# 8085_IO_LCD.net
KiCad netlist of a schematic drawn in EAGLE
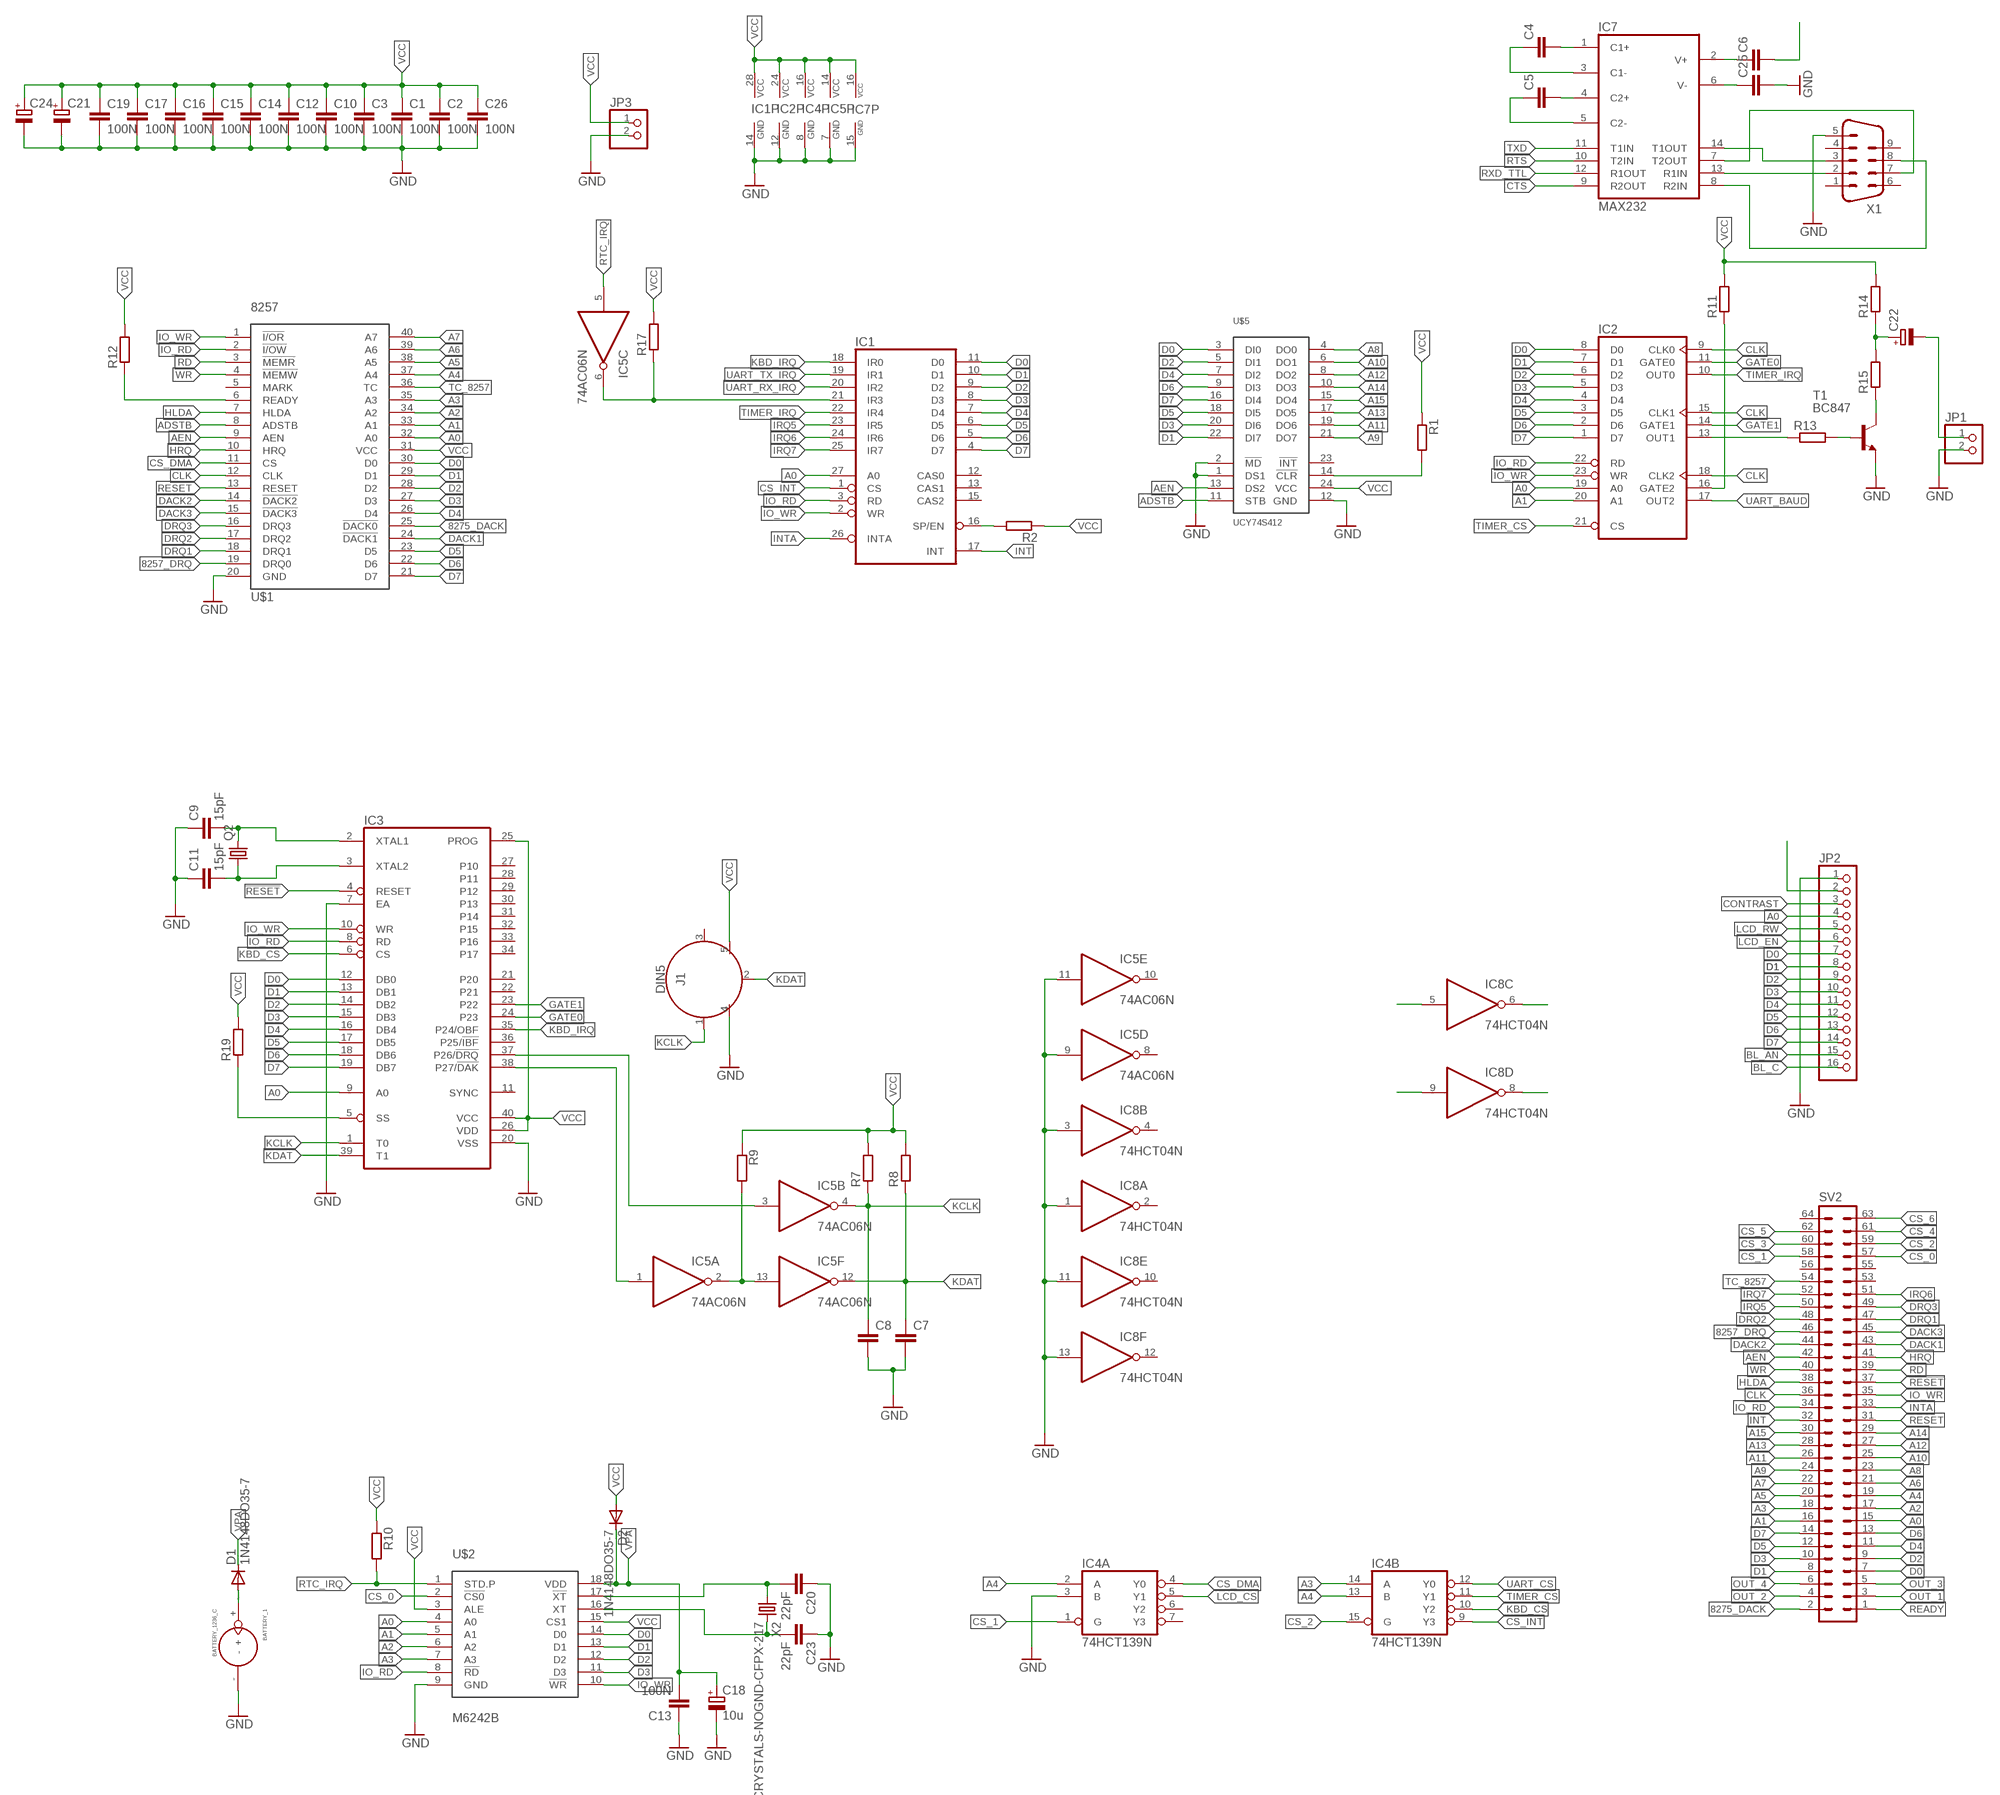
[diagram p0: schematic, sheet 1, part 1 of 2]
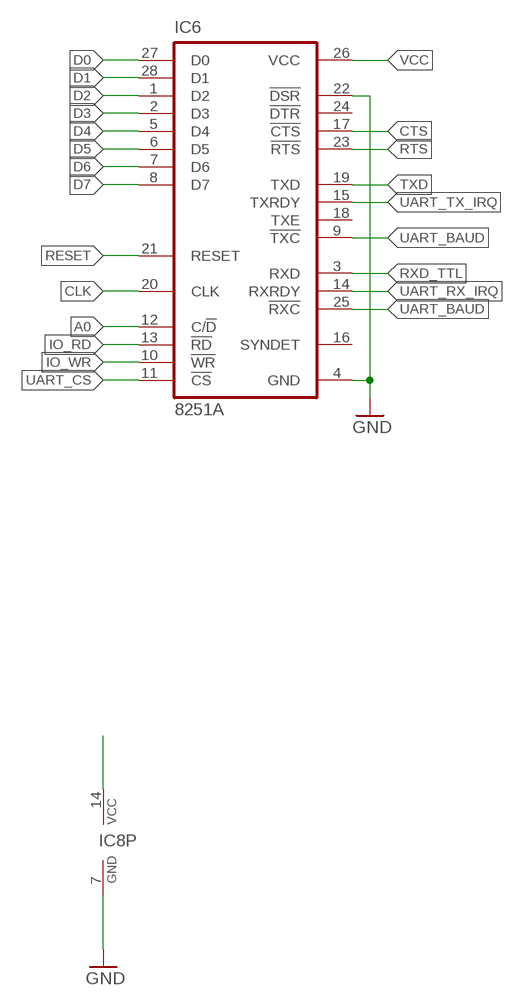
[diagram p1: schematic, sheet 1, part 2 of 2]

(export (version "E")
  (design (tool "Eeschema 10.0.6"))
  (components
    (comp (ref "BATTERY_1")
      (value "BATTERY_1236_C")
      (footprint "eagle-import:BATTERY_1236_C")
      (libsource (lib "eagle-import") (part "BATTERY_1236_C"))
    )
    (comp (ref "C1")
      (value "100N")
      (footprint "eagle-import:C0603")
      (libsource (lib "eagle-import") (part "C-EUC0603"))
    )
    (comp (ref "C2")
      (value "100N")
      (footprint "eagle-import:C1206")
      (libsource (lib "eagle-import") (part "C-EUC1206"))
    )
    (comp (ref "C3")
      (value "100N")
      (footprint "eagle-import:C0603")
      (libsource (lib "eagle-import") (part "C-EUC0603"))
    )
    (comp (ref "C4")
      (value "C-EUC0603")
      (footprint "eagle-import:C0603")
      (libsource (lib "eagle-import") (part "C-EUC0603"))
    )
    (comp (ref "C5")
      (value "C-EUC0603")
      (footprint "eagle-import:C0603")
      (libsource (lib "eagle-import") (part "C-EUC0603"))
    )
    (comp (ref "C6")
      (value "C-EUC0603")
      (footprint "eagle-import:C0603")
      (libsource (lib "eagle-import") (part "C-EUC0603"))
    )
    (comp (ref "C7")
      (value "C-EUC0603")
      (footprint "eagle-import:C0603")
      (libsource (lib "eagle-import") (part "C-EUC0603"))
    )
    (comp (ref "C8")
      (value "C-EUC0603")
      (footprint "eagle-import:C0603")
      (libsource (lib "eagle-import") (part "C-EUC0603"))
    )
    (comp (ref "C9")
      (value "15pF")
      (footprint "eagle-import:C0603")
      (libsource (lib "eagle-import") (part "C-EUC0603"))
    )
    (comp (ref "C10")
      (value "100N")
      (footprint "eagle-import:C0603")
      (libsource (lib "eagle-import") (part "C-EUC0603"))
    )
    (comp (ref "C11")
      (value "15pF")
      (footprint "eagle-import:C0603")
      (libsource (lib "eagle-import") (part "C-EUC0603"))
    )
    (comp (ref "C12")
      (value "100N")
      (footprint "eagle-import:C0603")
      (libsource (lib "eagle-import") (part "C-EUC0603"))
    )
    (comp (ref "C13")
      (value "100N")
      (footprint "eagle-import:C0603")
      (libsource (lib "eagle-import") (part "C-EUC0603"))
    )
    (comp (ref "C14")
      (value "100N")
      (footprint "eagle-import:C0603")
      (libsource (lib "eagle-import") (part "C-EUC0603"))
    )
    (comp (ref "C15")
      (value "100N")
      (footprint "eagle-import:C0603")
      (libsource (lib "eagle-import") (part "C-EUC0603"))
    )
    (comp (ref "C16")
      (value "100N")
      (footprint "eagle-import:C0603")
      (libsource (lib "eagle-import") (part "C-EUC0603"))
    )
    (comp (ref "C17")
      (value "100N")
      (footprint "eagle-import:C0603")
      (libsource (lib "eagle-import") (part "C-EUC0603"))
    )
    (comp (ref "C18")
      (value "10u")
      (footprint "eagle-import:SMC_B")
      (libsource (lib "eagle-import") (part "CPOL-EUSMCB"))
    )
    (comp (ref "C19")
      (value "100N")
      (footprint "eagle-import:C0603")
      (libsource (lib "eagle-import") (part "C-EUC0603"))
    )
    (comp (ref "C20")
      (value "22pF")
      (footprint "eagle-import:C0603")
      (libsource (lib "eagle-import") (part "C-EUC0603"))
    )
    (comp (ref "C21")
      (value "CPOL-EUE3.5-8")
      (footprint "eagle-import:E3,5-8")
      (libsource (lib "eagle-import") (part "CPOL-EUE3.5-8"))
    )
    (comp (ref "C22")
      (value "CPOL-EUE2-4")
      (footprint "eagle-import:E2-4")
      (libsource (lib "eagle-import") (part "CPOL-EUE2-4"))
    )
    (comp (ref "C23")
      (value "22pF")
      (footprint "eagle-import:C0603")
      (libsource (lib "eagle-import") (part "C-EUC0603"))
    )
    (comp (ref "C24")
      (value "CPOL-EUSMCB")
      (footprint "eagle-import:SMC_B")
      (libsource (lib "eagle-import") (part "CPOL-EUSMCB"))
    )
    (comp (ref "C25")
      (value "C-EUC0603")
      (footprint "eagle-import:C0603")
      (libsource (lib "eagle-import") (part "C-EUC0603"))
    )
    (comp (ref "C26")
      (value "100N")
      (footprint "eagle-import:C0805")
      (libsource (lib "eagle-import") (part "C-EUC0805"))
    )
    (comp (ref "D1")
      (value "1N4148DO35-7")
      (footprint "eagle-import:DO35-7")
      (libsource (lib "eagle-import") (part "1N4148DO35-7"))
    )
    (comp (ref "D2")
      (value "1N4148DO35-7")
      (footprint "eagle-import:DO35-7")
      (libsource (lib "eagle-import") (part "1N4148DO35-7"))
    )
    (comp (ref "IC1")
      (value "8259A")
      (footprint "eagle-import:DIL28-6")
      (libsource (lib "eagle-import") (part "8259A"))
    )
    (comp (ref "IC2")
      (value "8253")
      (footprint "eagle-import:DIL24-6")
      (libsource (lib "eagle-import") (part "8253"))
    )
    (comp (ref "IC3")
      (value "UPI-8042AH")
      (footprint "eagle-import:DIL40")
      (libsource (lib "eagle-import") (part "UPI-8042AH"))
    )
    (comp (ref "IC4")
      (value "74HCT139N")
      (footprint "eagle-import:DIL16")
      (libsource (lib "eagle-import") (part "74139NHCT"))
    )
    (comp (ref "IC5")
      (value "74AC06N")
      (footprint "eagle-import:DIL14")
      (libsource (lib "eagle-import") (part "7406NAC"))
    )
    (comp (ref "IC6")
      (value "8251A")
      (footprint "eagle-import:DIL28-6")
      (libsource (lib "eagle-import") (part "8251A"))
    )
    (comp (ref "IC7")
      (value "MAX232")
      (footprint "eagle-import:DIL16")
      (fields (field (name "MF") "MAXIM") (field (name "MPN") "MAX232ACPE+"))
      (libsource (lib "eagle-import") (part "MAX232"))
    )
    (comp (ref "IC8")
      (value "74HCT04N")
      (footprint "eagle-import:DIL14")
      (libsource (lib "eagle-import") (part "7404NHCT"))
    )
    (comp (ref "J1")
      (value "DIN5")
      (footprint "eagle-import:DIN5-RA-PTH")
      (libsource (lib "eagle-import") (part "DIN5"))
    )
    (comp (ref "JP1")
      (value "PINHD-1X2")
      (footprint "eagle-import:1X02")
      (libsource (lib "eagle-import") (part "PINHD-1X2"))
    )
    (comp (ref "JP2")
      (value "PINHD-1X16")
      (footprint "eagle-import:1X16")
      (libsource (lib "eagle-import") (part "PINHD-1X16"))
    )
    (comp (ref "JP3")
      (value "PINHD-1X2/90")
      (footprint "eagle-import:1X02_90")
      (libsource (lib "eagle-import") (part "PINHD-1X2/90"))
    )
    (comp (ref "Q2")
      (value "CRYSTALHC49S")
      (footprint "eagle-import:HC49_S")
      (libsource (lib "eagle-import") (part "CRYSTALHC49S"))
    )
    (comp (ref "R1")
      (value "R-EU_R0603")
      (footprint "eagle-import:R0603")
      (libsource (lib "eagle-import") (part "R-EU_R0603"))
    )
    (comp (ref "R2")
      (value "R-EU_R0603")
      (footprint "eagle-import:R0603")
      (libsource (lib "eagle-import") (part "R-EU_R0603"))
    )
    (comp (ref "R7")
      (value "R-EU_0204/5")
      (footprint "eagle-import:0204_5")
      (libsource (lib "eagle-import") (part "R-EU_0204/5"))
    )
    (comp (ref "R8")
      (value "R-EU_M0805")
      (footprint "eagle-import:M0805")
      (libsource (lib "eagle-import") (part "R-EU_M0805"))
    )
    (comp (ref "R9")
      (value "R-EU_R0603")
      (footprint "eagle-import:R0603")
      (libsource (lib "eagle-import") (part "R-EU_R0603"))
    )
    (comp (ref "R10")
      (value "R-EU_R0603")
      (footprint "eagle-import:R0603")
      (libsource (lib "eagle-import") (part "R-EU_R0603"))
    )
    (comp (ref "R11")
      (value "R-EU_R0603")
      (footprint "eagle-import:R0603")
      (libsource (lib "eagle-import") (part "R-EU_R0603"))
    )
    (comp (ref "R12")
      (value "R-EU_R0603")
      (footprint "eagle-import:R0603")
      (libsource (lib "eagle-import") (part "R-EU_R0603"))
    )
    (comp (ref "R13")
      (value "R-EU_R0603")
      (footprint "eagle-import:R0603")
      (libsource (lib "eagle-import") (part "R-EU_R0603"))
    )
    (comp (ref "R14")
      (value "R-EU_0204/5")
      (footprint "eagle-import:0204_5")
      (libsource (lib "eagle-import") (part "R-EU_0204/5"))
    )
    (comp (ref "R15")
      (value "R-EU_R0603")
      (footprint "eagle-import:R0603")
      (libsource (lib "eagle-import") (part "R-EU_R0603"))
    )
    (comp (ref "R17")
      (value "R-EU_0204/7")
      (footprint "eagle-import:0204_7")
      (libsource (lib "eagle-import") (part "R-EU_0204/7"))
    )
    (comp (ref "R19")
      (value "R-EU_0204/5")
      (footprint "eagle-import:0204_5")
      (libsource (lib "eagle-import") (part "R-EU_0204/5"))
    )
    (comp (ref "SV2")
      (value "ML64L")
      (footprint "eagle-import:ML64L")
      (libsource (lib "eagle-import") (part "ML64L"))
    )
    (comp (ref "T1")
      (value "BC847")
      (footprint "eagle-import:SOT23")
      (libsource (lib "eagle-import") (part "BC847"))
    )
    (comp (ref "U$1")
      (value "8257")
      (footprint "eagle-import:DIL40")
      (libsource (lib "eagle-import") (part "8257"))
    )
    (comp (ref "U$2")
      (value "M6242B")
      (footprint "eagle-import:DIL18")
      (libsource (lib "eagle-import") (part "M6242B"))
    )
    (comp (ref "U$5")
      (value "UCY74S412")
      (footprint "eagle-import:DIL24-6")
      (libsource (lib "eagle-import") (part "UCY74S412"))
    )
    (comp (ref "X1")
      (value "M09HP")
      (footprint "eagle-import:M09HP")
      (libsource (lib "eagle-import") (part "M09HP"))
    )
    (comp (ref "X2")
      (value "CRYSTALS-NOGND-CFPX-217")
      (footprint "eagle-import:3.2X1.5-2-PAD")
      (libsource (lib "eagle-import") (part "CRYSTALS-NOGND-CFPX-217"))
    )
  )
  (nets
    (net (code "1") (name "/~{RESET}") (class "Default")
      (node (ref "IC3") (pin "4") (pinfunction "RESET_4") (pintype "input"))
      (node (ref "SV2") (pin "37") (pinfunction "37_37") (pintype "passive"))
    )
    (net (code "2") (name "8257_DRQ") (class "Default")
      (node (ref "SV2") (pin "46") (pinfunction "46_46") (pintype "passive"))
      (node (ref "U$1") (pin "19") (pinfunction "DRQ0_19") (pintype "bidirectional"))
    )
    (net (code "3") (name "8275_DACK") (class "Default")
      (node (ref "SV2") (pin "2") (pinfunction "2_2") (pintype "passive"))
      (node (ref "U$1") (pin "25") (pinfunction "~{DACK0}_25") (pintype "bidirectional"))
    )
    (net (code "4") (name "A0") (class "Default")
      (node (ref "IC1") (pin "27") (pinfunction "A0_27") (pintype "input"))
      (node (ref "IC2") (pin "19") (pinfunction "A0_19") (pintype "input"))
      (node (ref "IC3") (pin "9") (pinfunction "A0_9") (pintype "input"))
      (node (ref "IC6") (pin "12") (pinfunction "C/~{D}_12") (pintype "input"))
      (node (ref "JP2") (pin "4") (pinfunction "4_4") (pintype "passive"))
      (node (ref "SV2") (pin "15") (pinfunction "15_15") (pintype "passive"))
      (node (ref "U$1") (pin "32") (pinfunction "A0_32") (pintype "bidirectional"))
      (node (ref "U$2") (pin "4") (pinfunction "A0_4") (pintype "bidirectional"))
    )
    (net (code "5") (name "A1") (class "Default")
      (node (ref "IC2") (pin "20") (pinfunction "A1_20") (pintype "input"))
      (node (ref "SV2") (pin "16") (pinfunction "16_16") (pintype "passive"))
      (node (ref "U$1") (pin "33") (pinfunction "A1_33") (pintype "bidirectional"))
      (node (ref "U$2") (pin "5") (pinfunction "A1_5") (pintype "bidirectional"))
    )
    (net (code "6") (name "A2") (class "Default")
      (node (ref "SV2") (pin "17") (pinfunction "17_17") (pintype "passive"))
      (node (ref "U$1") (pin "34") (pinfunction "A2_34") (pintype "bidirectional"))
      (node (ref "U$2") (pin "6") (pinfunction "A2_6") (pintype "bidirectional"))
    )
    (net (code "7") (name "A3") (class "Default")
      (node (ref "IC4") (pin "14") (pinfunction "A_14") (pintype "input"))
      (node (ref "SV2") (pin "18") (pinfunction "18_18") (pintype "passive"))
      (node (ref "U$1") (pin "35") (pinfunction "A3_35") (pintype "bidirectional"))
      (node (ref "U$2") (pin "7") (pinfunction "A3_7") (pintype "bidirectional"))
    )
    (net (code "8") (name "A4") (class "Default")
      (node (ref "IC4") (pin "13") (pinfunction "B_13") (pintype "input"))
      (node (ref "IC4") (pin "2") (pinfunction "A_2") (pintype "input"))
      (node (ref "SV2") (pin "19") (pinfunction "19_19") (pintype "passive"))
      (node (ref "U$1") (pin "37") (pinfunction "A4_37") (pintype "bidirectional"))
    )
    (net (code "9") (name "A5") (class "Default")
      (node (ref "SV2") (pin "20") (pinfunction "20_20") (pintype "passive"))
      (node (ref "U$1") (pin "38") (pinfunction "A5_38") (pintype "bidirectional"))
    )
    (net (code "10") (name "A6") (class "Default")
      (node (ref "SV2") (pin "21") (pinfunction "21_21") (pintype "passive"))
      (node (ref "U$1") (pin "39") (pinfunction "A6_39") (pintype "bidirectional"))
    )
    (net (code "11") (name "A7") (class "Default")
      (node (ref "SV2") (pin "22") (pinfunction "22_22") (pintype "passive"))
      (node (ref "U$1") (pin "40") (pinfunction "A7_40") (pintype "bidirectional"))
    )
    (net (code "12") (name "A8") (class "Default")
      (node (ref "SV2") (pin "23") (pinfunction "23_23") (pintype "passive"))
      (node (ref "U$5") (pin "4") (pinfunction "DO0_4") (pintype "bidirectional"))
    )
    (net (code "13") (name "A9") (class "Default")
      (node (ref "SV2") (pin "24") (pinfunction "24_24") (pintype "passive"))
      (node (ref "U$5") (pin "21") (pinfunction "DO7_21") (pintype "bidirectional"))
    )
    (net (code "14") (name "A10") (class "Default")
      (node (ref "SV2") (pin "25") (pinfunction "25_25") (pintype "passive"))
      (node (ref "U$5") (pin "6") (pinfunction "DO1_6") (pintype "bidirectional"))
    )
    (net (code "15") (name "A11") (class "Default")
      (node (ref "SV2") (pin "26") (pinfunction "26_26") (pintype "passive"))
      (node (ref "U$5") (pin "19") (pinfunction "DO6_19") (pintype "bidirectional"))
    )
    (net (code "16") (name "A12") (class "Default")
      (node (ref "SV2") (pin "27") (pinfunction "27_27") (pintype "passive"))
      (node (ref "U$5") (pin "8") (pinfunction "DO2_8") (pintype "bidirectional"))
    )
    (net (code "17") (name "A13") (class "Default")
      (node (ref "SV2") (pin "28") (pinfunction "28_28") (pintype "passive"))
      (node (ref "U$5") (pin "17") (pinfunction "DO5_17") (pintype "bidirectional"))
    )
    (net (code "18") (name "A14") (class "Default")
      (node (ref "SV2") (pin "29") (pinfunction "29_29") (pintype "passive"))
      (node (ref "U$5") (pin "10") (pinfunction "DO3_10") (pintype "bidirectional"))
    )
    (net (code "19") (name "A15") (class "Default")
      (node (ref "SV2") (pin "30") (pinfunction "30_30") (pintype "passive"))
      (node (ref "U$5") (pin "15") (pinfunction "DO4_15") (pintype "bidirectional"))
    )
    (net (code "20") (name "ADSTB") (class "Default")
      (node (ref "U$1") (pin "8") (pinfunction "ADSTB_8") (pintype "bidirectional"))
      (node (ref "U$5") (pin "11") (pinfunction "STB_11") (pintype "bidirectional"))
    )
    (net (code "21") (name "AEN") (class "Default")
      (node (ref "SV2") (pin "42") (pinfunction "42_42") (pintype "passive"))
      (node (ref "U$1") (pin "9") (pinfunction "AEN_9") (pintype "bidirectional"))
      (node (ref "U$5") (pin "13") (pinfunction "DS2_13") (pintype "bidirectional"))
    )
    (net (code "22") (name "BL_AN") (class "Default")
      (node (ref "JP2") (pin "15") (pinfunction "15_15") (pintype "passive"))
    )
    (net (code "23") (name "BL_C") (class "Default")
      (node (ref "JP2") (pin "16") (pinfunction "16_16") (pintype "passive"))
    )
    (net (code "24") (name "CLK") (class "Default")
      (node (ref "IC2") (pin "15") (pinfunction "CLK1_15") (pintype "input"))
      (node (ref "IC2") (pin "18") (pinfunction "CLK2_18") (pintype "input"))
      (node (ref "IC2") (pin "9") (pinfunction "CLK0_9") (pintype "input"))
      (node (ref "IC6") (pin "20") (pinfunction "CLK_20") (pintype "input"))
      (node (ref "SV2") (pin "36") (pinfunction "36_36") (pintype "passive"))
      (node (ref "U$1") (pin "12") (pinfunction "CLK_12") (pintype "bidirectional"))
    )
    (net (code "25") (name "CONTRAST") (class "Default")
      (node (ref "JP2") (pin "3") (pinfunction "3_3") (pintype "passive"))
    )
    (net (code "26") (name "CS_0") (class "Default")
      (node (ref "SV2") (pin "57") (pinfunction "57_57") (pintype "passive"))
      (node (ref "U$2") (pin "2") (pinfunction "~{CS0}_2") (pintype "bidirectional"))
    )
    (net (code "27") (name "CS_1") (class "Default")
      (node (ref "IC4") (pin "1") (pinfunction "G_1") (pintype "input"))
      (node (ref "SV2") (pin "58") (pinfunction "58_58") (pintype "passive"))
    )
    (net (code "28") (name "CS_2") (class "Default")
      (node (ref "IC4") (pin "15") (pinfunction "G_15") (pintype "input"))
      (node (ref "SV2") (pin "59") (pinfunction "59_59") (pintype "passive"))
    )
    (net (code "29") (name "CS_3") (class "Default")
      (node (ref "SV2") (pin "60") (pinfunction "60_60") (pintype "passive"))
    )
    (net (code "30") (name "CS_4") (class "Default")
      (node (ref "SV2") (pin "61") (pinfunction "61_61") (pintype "passive"))
    )
    (net (code "31") (name "CS_5") (class "Default")
      (node (ref "SV2") (pin "62") (pinfunction "62_62") (pintype "passive"))
    )
    (net (code "32") (name "CS_6") (class "Default")
      (node (ref "SV2") (pin "63") (pinfunction "63_63") (pintype "passive"))
    )
    (net (code "33") (name "CS_DMA") (class "Default")
      (node (ref "IC4") (pin "4") (pinfunction "Y0_4") (pintype "output"))
      (node (ref "U$1") (pin "11") (pinfunction "CS_11") (pintype "bidirectional"))
    )
    (net (code "34") (name "CS_INT") (class "Default")
      (node (ref "IC1") (pin "1") (pinfunction "CS_1") (pintype "input"))
      (node (ref "IC4") (pin "9") (pinfunction "Y3_9") (pintype "output"))
    )
    (net (code "35") (name "CTS") (class "Default")
      (node (ref "IC6") (pin "17") (pinfunction "~{CTS}_17") (pintype "input"))
      (node (ref "IC7") (pin "9") (pinfunction "R2OUT_9") (pintype "output"))
    )
    (net (code "36") (name "D0") (class "Default")
      (node (ref "IC1") (pin "11") (pinfunction "D0_11") (pintype "bidirectional"))
      (node (ref "IC2") (pin "8") (pinfunction "D0_8") (pintype "bidirectional"))
      (node (ref "IC3") (pin "12") (pinfunction "DB0_12") (pintype "bidirectional"))
      (node (ref "IC6") (pin "27") (pinfunction "D0_27") (pintype "tri_state"))
      (node (ref "JP2") (pin "7") (pinfunction "7_7") (pintype "passive"))
      (node (ref "SV2") (pin "7") (pinfunction "7_7") (pintype "passive"))
      (node (ref "U$1") (pin "30") (pinfunction "D0_30") (pintype "bidirectional"))
      (node (ref "U$2") (pin "14") (pinfunction "D0_14") (pintype "bidirectional"))
      (node (ref "U$5") (pin "3") (pinfunction "DI0_3") (pintype "bidirectional"))
    )
    (net (code "37") (name "D1") (class "Default")
      (node (ref "IC1") (pin "10") (pinfunction "D1_10") (pintype "bidirectional"))
      (node (ref "IC2") (pin "7") (pinfunction "D1_7") (pintype "bidirectional"))
      (node (ref "IC3") (pin "13") (pinfunction "DB1_13") (pintype "bidirectional"))
      (node (ref "IC6") (pin "28") (pinfunction "D1_28") (pintype "tri_state"))
      (node (ref "JP2") (pin "8") (pinfunction "8_8") (pintype "passive"))
      (node (ref "SV2") (pin "8") (pinfunction "8_8") (pintype "passive"))
      (node (ref "U$1") (pin "29") (pinfunction "D1_29") (pintype "bidirectional"))
      (node (ref "U$2") (pin "13") (pinfunction "D1_13") (pintype "bidirectional"))
      (node (ref "U$5") (pin "22") (pinfunction "DI7_22") (pintype "bidirectional"))
    )
    (net (code "38") (name "D2") (class "Default")
      (node (ref "IC1") (pin "9") (pinfunction "D2_9") (pintype "bidirectional"))
      (node (ref "IC2") (pin "6") (pinfunction "D2_6") (pintype "bidirectional"))
      (node (ref "IC3") (pin "14") (pinfunction "DB2_14") (pintype "bidirectional"))
      (node (ref "IC6") (pin "1") (pinfunction "D2_1") (pintype "tri_state"))
      (node (ref "JP2") (pin "9") (pinfunction "9_9") (pintype "passive"))
      (node (ref "SV2") (pin "9") (pinfunction "9_9") (pintype "passive"))
      (node (ref "U$1") (pin "28") (pinfunction "D2_28") (pintype "bidirectional"))
      (node (ref "U$2") (pin "12") (pinfunction "D2_12") (pintype "bidirectional"))
      (node (ref "U$5") (pin "5") (pinfunction "DI1_5") (pintype "bidirectional"))
    )
    (net (code "39") (name "D3") (class "Default")
      (node (ref "IC1") (pin "8") (pinfunction "D3_8") (pintype "bidirectional"))
      (node (ref "IC2") (pin "5") (pinfunction "D3_5") (pintype "bidirectional"))
      (node (ref "IC3") (pin "15") (pinfunction "DB3_15") (pintype "bidirectional"))
      (node (ref "IC6") (pin "2") (pinfunction "D3_2") (pintype "tri_state"))
      (node (ref "JP2") (pin "10") (pinfunction "10_10") (pintype "passive"))
      (node (ref "SV2") (pin "10") (pinfunction "10_10") (pintype "passive"))
      (node (ref "U$1") (pin "27") (pinfunction "D3_27") (pintype "bidirectional"))
      (node (ref "U$2") (pin "11") (pinfunction "D3_11") (pintype "bidirectional"))
      (node (ref "U$5") (pin "20") (pinfunction "DI6_20") (pintype "bidirectional"))
    )
    (net (code "40") (name "D4") (class "Default")
      (node (ref "IC1") (pin "7") (pinfunction "D4_7") (pintype "bidirectional"))
      (node (ref "IC2") (pin "4") (pinfunction "D4_4") (pintype "bidirectional"))
      (node (ref "IC3") (pin "16") (pinfunction "DB4_16") (pintype "bidirectional"))
      (node (ref "IC6") (pin "5") (pinfunction "D4_5") (pintype "tri_state"))
      (node (ref "JP2") (pin "11") (pinfunction "11_11") (pintype "passive"))
      (node (ref "SV2") (pin "11") (pinfunction "11_11") (pintype "passive"))
      (node (ref "U$1") (pin "26") (pinfunction "D4_26") (pintype "bidirectional"))
      (node (ref "U$5") (pin "7") (pinfunction "DI2_7") (pintype "bidirectional"))
    )
    (net (code "41") (name "D5") (class "Default")
      (node (ref "IC1") (pin "6") (pinfunction "D5_6") (pintype "bidirectional"))
      (node (ref "IC2") (pin "3") (pinfunction "D5_3") (pintype "bidirectional"))
      (node (ref "IC3") (pin "17") (pinfunction "DB5_17") (pintype "bidirectional"))
      (node (ref "IC6") (pin "6") (pinfunction "D5_6") (pintype "tri_state"))
      (node (ref "JP2") (pin "12") (pinfunction "12_12") (pintype "passive"))
      (node (ref "SV2") (pin "12") (pinfunction "12_12") (pintype "passive"))
      (node (ref "U$1") (pin "23") (pinfunction "D5_23") (pintype "bidirectional"))
      (node (ref "U$5") (pin "18") (pinfunction "DI5_18") (pintype "bidirectional"))
    )
    (net (code "42") (name "D6") (class "Default")
      (node (ref "IC1") (pin "5") (pinfunction "D6_5") (pintype "bidirectional"))
      (node (ref "IC2") (pin "2") (pinfunction "D6_2") (pintype "bidirectional"))
      (node (ref "IC3") (pin "18") (pinfunction "DB6_18") (pintype "bidirectional"))
      (node (ref "IC6") (pin "7") (pinfunction "D6_7") (pintype "tri_state"))
      (node (ref "JP2") (pin "13") (pinfunction "13_13") (pintype "passive"))
      (node (ref "SV2") (pin "13") (pinfunction "13_13") (pintype "passive"))
      (node (ref "U$1") (pin "22") (pinfunction "D6_22") (pintype "bidirectional"))
      (node (ref "U$5") (pin "9") (pinfunction "DI3_9") (pintype "bidirectional"))
    )
    (net (code "43") (name "D7") (class "Default")
      (node (ref "IC1") (pin "4") (pinfunction "D7_4") (pintype "bidirectional"))
      (node (ref "IC2") (pin "1") (pinfunction "D7_1") (pintype "bidirectional"))
      (node (ref "IC3") (pin "19") (pinfunction "DB7_19") (pintype "bidirectional"))
      (node (ref "IC6") (pin "8") (pinfunction "D7_8") (pintype "tri_state"))
      (node (ref "JP2") (pin "14") (pinfunction "14_14") (pintype "passive"))
      (node (ref "SV2") (pin "14") (pinfunction "14_14") (pintype "passive"))
      (node (ref "U$1") (pin "21") (pinfunction "D7_21") (pintype "bidirectional"))
      (node (ref "U$5") (pin "16") (pinfunction "DI4_16") (pintype "bidirectional"))
    )
    (net (code "44") (name "DACK1") (class "Default")
      (node (ref "SV2") (pin "43") (pinfunction "43_43") (pintype "passive"))
      (node (ref "U$1") (pin "24") (pinfunction "~{DACK1}_24") (pintype "bidirectional"))
    )
    (net (code "45") (name "DACK2") (class "Default")
      (node (ref "SV2") (pin "44") (pinfunction "44_44") (pintype "passive"))
      (node (ref "U$1") (pin "14") (pinfunction "~{DACK2}_14") (pintype "bidirectional"))
    )
    (net (code "46") (name "DACK3") (class "Default")
      (node (ref "SV2") (pin "45") (pinfunction "45_45") (pintype "passive"))
      (node (ref "U$1") (pin "15") (pinfunction "~{DACK3}_15") (pintype "bidirectional"))
    )
    (net (code "47") (name "DRQ1") (class "Default")
      (node (ref "SV2") (pin "47") (pinfunction "47_47") (pintype "passive"))
      (node (ref "U$1") (pin "18") (pinfunction "DRQ1_18") (pintype "bidirectional"))
    )
    (net (code "48") (name "DRQ2") (class "Default")
      (node (ref "SV2") (pin "48") (pinfunction "48_48") (pintype "passive"))
      (node (ref "U$1") (pin "17") (pinfunction "DRQ2_17") (pintype "bidirectional"))
    )
    (net (code "49") (name "DRQ3") (class "Default")
      (node (ref "SV2") (pin "49") (pinfunction "49_49") (pintype "passive"))
      (node (ref "U$1") (pin "16") (pinfunction "DRQ3_16") (pintype "bidirectional"))
    )
    (net (code "50") (name "GATE0") (class "Default")
      (node (ref "IC2") (pin "11") (pinfunction "GATE0_11") (pintype "input"))
      (node (ref "IC3") (pin "24") (pinfunction "P23_24") (pintype "bidirectional"))
    )
    (net (code "51") (name "GATE1") (class "Default")
      (node (ref "IC2") (pin "14") (pinfunction "GATE1_14") (pintype "input"))
      (node (ref "IC3") (pin "23") (pinfunction "P22_23") (pintype "bidirectional"))
    )
    (net (code "52") (name "GND") (class "Default")
      (node (ref "BATTERY_1") (pin "-") (pinfunction "-_-") (pintype "bidirectional"))
      (node (ref "C1") (pin "2") (pinfunction "2_2") (pintype "passive"))
      (node (ref "C10") (pin "2") (pinfunction "2_2") (pintype "passive"))
      (node (ref "C11") (pin "1") (pinfunction "1_1") (pintype "passive"))
      (node (ref "C12") (pin "2") (pinfunction "2_2") (pintype "passive"))
      (node (ref "C13") (pin "1") (pinfunction "1_1") (pintype "passive"))
      (node (ref "C14") (pin "2") (pinfunction "2_2") (pintype "passive"))
      (node (ref "C15") (pin "2") (pinfunction "2_2") (pintype "passive"))
      (node (ref "C16") (pin "2") (pinfunction "2_2") (pintype "passive"))
      (node (ref "C17") (pin "2") (pinfunction "2_2") (pintype "passive"))
      (node (ref "C18") (pin "-") (pinfunction "-_-") (pintype "passive"))
      (node (ref "C19") (pin "2") (pinfunction "2_2") (pintype "passive"))
      (node (ref "C2") (pin "2") (pinfunction "2_2") (pintype "passive"))
      (node (ref "C20") (pin "1") (pinfunction "1_1") (pintype "passive"))
      (node (ref "C21") (pin "-") (pinfunction "-_-") (pintype "passive"))
      (node (ref "C23") (pin "1") (pinfunction "1_1") (pintype "passive"))
      (node (ref "C24") (pin "-") (pinfunction "-_-") (pintype "passive"))
      (node (ref "C25") (pin "2") (pinfunction "2_2") (pintype "passive"))
      (node (ref "C26") (pin "2") (pinfunction "2_2") (pintype "passive"))
      (node (ref "C3") (pin "2") (pinfunction "2_2") (pintype "passive"))
      (node (ref "C7") (pin "2") (pinfunction "2_2") (pintype "passive"))
      (node (ref "C8") (pin "2") (pinfunction "2_2") (pintype "passive"))
      (node (ref "C9") (pin "1") (pinfunction "1_1") (pintype "passive"))
      (node (ref "IC1") (pin "14") (pinfunction "GND_14") (pintype "power_in"))
      (node (ref "IC2") (pin "12") (pinfunction "GND_12") (pintype "power_in"))
      (node (ref "IC3") (pin "20") (pinfunction "VSS_20") (pintype "power_in"))
      (node (ref "IC3") (pin "7") (pinfunction "EA_7") (pintype "input"))
      (node (ref "IC4") (pin "3") (pinfunction "B_3") (pintype "input"))
      (node (ref "IC4") (pin "8") (pinfunction "GND_8") (pintype "power_in"))
      (node (ref "IC5") (pin "11") (pinfunction "I_11") (pintype "input"))
      (node (ref "IC5") (pin "7") (pinfunction "GND_7") (pintype "power_in"))
      (node (ref "IC5") (pin "9") (pinfunction "I_9") (pintype "input"))
      (node (ref "IC6") (pin "22") (pinfunction "~{DSR}_22") (pintype "input"))
      (node (ref "IC6") (pin "4") (pinfunction "GND_4") (pintype "power_in"))
      (node (ref "IC7") (pin "15") (pinfunction "GND_15") (pintype "power_in"))
      (node (ref "IC8") (pin "1") (pinfunction "I_1") (pintype "input"))
      (node (ref "IC8") (pin "11") (pinfunction "I_11") (pintype "input"))
      (node (ref "IC8") (pin "13") (pinfunction "I_13") (pintype "input"))
      (node (ref "IC8") (pin "3") (pinfunction "I_3") (pintype "input"))
      (node (ref "IC8") (pin "7") (pinfunction "GND_7") (pintype "power_in"))
      (node (ref "J1") (pin "4") (pinfunction "4_4") (pintype "bidirectional"))
      (node (ref "JP1") (pin "2") (pinfunction "2_2") (pintype "passive"))
      (node (ref "JP2") (pin "1") (pinfunction "1_1") (pintype "passive"))
      (node (ref "JP3") (pin "2") (pinfunction "2_2") (pintype "passive"))
      (node (ref "T1") (pin "2") (pinfunction "E_2") (pintype "passive"))
      (node (ref "U$1") (pin "20") (pinfunction "GND_20") (pintype "bidirectional"))
      (node (ref "U$2") (pin "9") (pinfunction "GND_9") (pintype "bidirectional"))
      (node (ref "U$5") (pin "1") (pinfunction "DS1_1") (pintype "bidirectional"))
      (node (ref "U$5") (pin "12") (pinfunction "GND_12") (pintype "bidirectional"))
      (node (ref "U$5") (pin "2") (pinfunction "~{MD}_2") (pintype "bidirectional"))
      (node (ref "X1") (pin "5") (pinfunction "5_5") (pintype "passive"))
    )
    (net (code "53") (name "HLDA") (class "Default")
      (node (ref "SV2") (pin "38") (pinfunction "38_38") (pintype "passive"))
      (node (ref "U$1") (pin "7") (pinfunction "HLDA_7") (pintype "bidirectional"))
    )
    (net (code "54") (name "HRQ") (class "Default")
      (node (ref "SV2") (pin "41") (pinfunction "41_41") (pintype "passive"))
      (node (ref "U$1") (pin "10") (pinfunction "HRQ_10") (pintype "bidirectional"))
    )
    (net (code "55") (name "INT") (class "Default")
      (node (ref "IC1") (pin "17") (pinfunction "INT_17") (pintype "output"))
      (node (ref "SV2") (pin "32") (pinfunction "32_32") (pintype "passive"))
    )
    (net (code "56") (name "INTA") (class "Default")
      (node (ref "IC1") (pin "26") (pinfunction "INTA_26") (pintype "input"))
      (node (ref "SV2") (pin "33") (pinfunction "33_33") (pintype "passive"))
    )
    (net (code "57") (name "IO_RD") (class "Default")
      (node (ref "IC1") (pin "3") (pinfunction "RD_3") (pintype "input"))
      (node (ref "IC2") (pin "22") (pinfunction "RD_22") (pintype "input"))
      (node (ref "IC3") (pin "8") (pinfunction "RD_8") (pintype "input"))
      (node (ref "IC6") (pin "13") (pinfunction "~{RD}_13") (pintype "input"))
      (node (ref "IC8") (pin "5") (pinfunction "I_5") (pintype "input"))
      (node (ref "SV2") (pin "34") (pinfunction "34_34") (pintype "passive"))
      (node (ref "U$1") (pin "2") (pinfunction "~{I/OW}_2") (pintype "bidirectional"))
      (node (ref "U$2") (pin "8") (pinfunction "~{RD}_8") (pintype "bidirectional"))
    )
    (net (code "58") (name "IO_WR") (class "Default")
      (node (ref "IC1") (pin "2") (pinfunction "WR_2") (pintype "input"))
      (node (ref "IC2") (pin "23") (pinfunction "WR_23") (pintype "input"))
      (node (ref "IC3") (pin "10") (pinfunction "WR_10") (pintype "input"))
      (node (ref "IC6") (pin "10") (pinfunction "~{WR}_10") (pintype "input"))
      (node (ref "SV2") (pin "35") (pinfunction "35_35") (pintype "passive"))
      (node (ref "U$1") (pin "1") (pinfunction "~{I/OR}_1") (pintype "bidirectional"))
      (node (ref "U$2") (pin "10") (pinfunction "~{WR}_10") (pintype "bidirectional"))
    )
    (net (code "59") (name "IRQ5") (class "Default")
      (node (ref "IC1") (pin "23") (pinfunction "IR5_23") (pintype "input"))
      (node (ref "SV2") (pin "50") (pinfunction "50_50") (pintype "passive"))
    )
    (net (code "60") (name "IRQ6") (class "Default")
      (node (ref "IC1") (pin "24") (pinfunction "IR6_24") (pintype "input"))
      (node (ref "SV2") (pin "51") (pinfunction "51_51") (pintype "passive"))
    )
    (net (code "61") (name "IRQ7") (class "Default")
      (node (ref "IC1") (pin "25") (pinfunction "IR7_25") (pintype "input"))
      (node (ref "SV2") (pin "52") (pinfunction "52_52") (pintype "passive"))
    )
    (net (code "62") (name "KBD_CS") (class "Default")
      (node (ref "IC3") (pin "6") (pinfunction "CS_6") (pintype "input"))
      (node (ref "IC4") (pin "10") (pinfunction "Y2_10") (pintype "output"))
    )
    (net (code "63") (name "KBD_IRQ") (class "Default")
      (node (ref "IC1") (pin "18") (pinfunction "IR0_18") (pintype "input"))
      (node (ref "IC3") (pin "35") (pinfunction "P24/OBF_35") (pintype "bidirectional"))
    )
    (net (code "64") (name "KCLK") (class "Default")
      (node (ref "C8") (pin "1") (pinfunction "1_1") (pintype "passive"))
      (node (ref "IC3") (pin "1") (pinfunction "T0_1") (pintype "input"))
      (node (ref "IC5") (pin "4") (pinfunction "O_4") (pintype "open_collector"))
      (node (ref "J1") (pin "1") (pinfunction "1_1") (pintype "bidirectional"))
      (node (ref "R7") (pin "1") (pinfunction "1_1") (pintype "passive"))
    )
    (net (code "65") (name "KDAT") (class "Default")
      (node (ref "C7") (pin "1") (pinfunction "1_1") (pintype "passive"))
      (node (ref "IC3") (pin "39") (pinfunction "T1_39") (pintype "input"))
      (node (ref "IC5") (pin "12") (pinfunction "O_12") (pintype "open_collector"))
      (node (ref "J1") (pin "2") (pinfunction "2_2") (pintype "bidirectional"))
      (node (ref "R8") (pin "1") (pinfunction "1_1") (pintype "passive"))
    )
    (net (code "66") (name "LCD_CS") (class "Default")
      (node (ref "IC4") (pin "5") (pinfunction "Y1_5") (pintype "output"))
      (node (ref "IC8") (pin "9") (pinfunction "I_9") (pintype "input"))
    )
    (net (code "67") (name "LCD_EN") (class "Default")
      (node (ref "IC8") (pin "8") (pinfunction "O_8") (pintype "output"))
      (node (ref "JP2") (pin "6") (pinfunction "6_6") (pintype "passive"))
    )
    (net (code "68") (name "LCD_RW") (class "Default")
      (node (ref "IC8") (pin "6") (pinfunction "O_6") (pintype "output"))
      (node (ref "JP2") (pin "5") (pinfunction "5_5") (pintype "passive"))
    )
    (net (code "69") (name "Net-(BATTERY_1-Pad+)") (class "Default")
      (node (ref "BATTERY_1") (pin "+") (pinfunction "+_+") (pintype "bidirectional"))
      (node (ref "D1") (pin "A") (pinfunction "A_A") (pintype "passive"))
    )
    (net (code "70") (name "Net-(C22-Pad+)") (class "Default")
      (node (ref "C22") (pin "+") (pinfunction "+_+") (pintype "passive"))
      (node (ref "R14") (pin "1") (pinfunction "1_1") (pintype "passive"))
      (node (ref "R15") (pin "2") (pinfunction "2_2") (pintype "passive"))
    )
    (net (code "71") (name "Net-(C22-Pad-)") (class "Default")
      (node (ref "C22") (pin "-") (pinfunction "-_-") (pintype "passive"))
      (node (ref "JP1") (pin "1") (pinfunction "1_1") (pintype "passive"))
    )
    (net (code "72") (name "Net-(IC1A-IR3)") (class "Default")
      (node (ref "IC1") (pin "21") (pinfunction "IR3_21") (pintype "input"))
      (node (ref "IC5") (pin "6") (pinfunction "O_6") (pintype "open_collector"))
      (node (ref "R17") (pin "1") (pinfunction "1_1") (pintype "passive"))
    )
    (net (code "73") (name "Net-(IC1A-SP{slash}EN)") (class "Default")
      (node (ref "IC1") (pin "16") (pinfunction "SP/EN_16") (pintype "bidirectional"))
      (node (ref "R2") (pin "2") (pinfunction "2_2") (pintype "passive"))
    )
    (net (code "74") (name "Net-(IC2A-GATE2)") (class "Default")
      (node (ref "IC2") (pin "16") (pinfunction "GATE2_16") (pintype "input"))
      (node (ref "R11") (pin "1") (pinfunction "1_1") (pintype "passive"))
    )
    (net (code "75") (name "Net-(IC2A-OUT1)") (class "Default")
      (node (ref "IC2") (pin "13") (pinfunction "OUT1_13") (pintype "output"))
      (node (ref "R13") (pin "1") (pinfunction "1_1") (pintype "passive"))
    )
    (net (code "76") (name "Net-(IC3-P26{slash}~{DRQ})") (class "Default")
      (node (ref "IC3") (pin "37") (pinfunction "P26/~{DRQ}_37") (pintype "bidirectional"))
      (node (ref "IC5") (pin "3") (pinfunction "I_3") (pintype "input"))
    )
    (net (code "77") (name "Net-(IC3-P27{slash}~{DAK})") (class "Default")
      (node (ref "IC3") (pin "38") (pinfunction "P27/~{DAK}_38") (pintype "bidirectional"))
      (node (ref "IC5") (pin "1") (pinfunction "I_1") (pintype "input"))
    )
    (net (code "78") (name "Net-(IC3-SS)") (class "Default")
      (node (ref "IC3") (pin "5") (pinfunction "SS_5") (pintype "input"))
      (node (ref "R19") (pin "1") (pinfunction "1_1") (pintype "passive"))
    )
    (net (code "79") (name "Net-(IC3-XTAL1)") (class "Default")
      (node (ref "C9") (pin "2") (pinfunction "2_2") (pintype "passive"))
      (node (ref "IC3") (pin "2") (pinfunction "XTAL1_2") (pintype "input"))
      (node (ref "Q2") (pin "2") (pinfunction "2_2") (pintype "passive"))
    )
    (net (code "80") (name "Net-(IC3-XTAL2)") (class "Default")
      (node (ref "C11") (pin "2") (pinfunction "2_2") (pintype "passive"))
      (node (ref "IC3") (pin "3") (pinfunction "XTAL2_3") (pintype "input"))
      (node (ref "Q2") (pin "1") (pinfunction "1_1") (pintype "passive"))
    )
    (net (code "81") (name "Net-(IC5A-O)") (class "Default")
      (node (ref "IC5") (pin "13") (pinfunction "I_13") (pintype "input"))
      (node (ref "IC5") (pin "2") (pinfunction "O_2") (pintype "open_collector"))
      (node (ref "R9") (pin "2") (pinfunction "2_2") (pintype "passive"))
    )
    (net (code "82") (name "Net-(IC7A-C1+)") (class "Default")
      (node (ref "C4") (pin "2") (pinfunction "2_2") (pintype "passive"))
      (node (ref "IC7") (pin "1") (pinfunction "C1+_1") (pintype "bidirectional"))
    )
    (net (code "83") (name "Net-(IC7A-C1-)") (class "Default")
      (node (ref "C4") (pin "1") (pinfunction "1_1") (pintype "passive"))
      (node (ref "IC7") (pin "3") (pinfunction "C1-_3") (pintype "bidirectional"))
    )
    (net (code "84") (name "Net-(IC7A-C2+)") (class "Default")
      (node (ref "C5") (pin "2") (pinfunction "2_2") (pintype "passive"))
      (node (ref "IC7") (pin "4") (pinfunction "C2+_4") (pintype "bidirectional"))
    )
    (net (code "85") (name "Net-(IC7A-C2-)") (class "Default")
      (node (ref "C5") (pin "1") (pinfunction "1_1") (pintype "passive"))
      (node (ref "IC7") (pin "5") (pinfunction "C2-_5") (pintype "bidirectional"))
    )
    (net (code "86") (name "Net-(IC7A-R1IN)") (class "Default")
      (node (ref "IC7") (pin "13") (pinfunction "R1IN_13") (pintype "input"))
      (node (ref "X1") (pin "2") (pinfunction "2_2") (pintype "passive"))
    )
    (net (code "87") (name "Net-(IC7A-R2IN)") (class "Default")
      (node (ref "IC7") (pin "8") (pinfunction "R2IN_8") (pintype "input"))
      (node (ref "X1") (pin "8") (pinfunction "8_8") (pintype "passive"))
    )
    (net (code "88") (name "Net-(IC7A-T1OUT)") (class "Default")
      (node (ref "IC7") (pin "14") (pinfunction "T1OUT_14") (pintype "output"))
      (node (ref "X1") (pin "3") (pinfunction "3_3") (pintype "passive"))
    )
    (net (code "89") (name "Net-(IC7A-T2OUT)") (class "Default")
      (node (ref "IC7") (pin "7") (pinfunction "T2OUT_7") (pintype "output"))
      (node (ref "X1") (pin "7") (pinfunction "7_7") (pintype "passive"))
    )
    (net (code "90") (name "Net-(IC7A-V+)") (class "Default")
      (node (ref "C6") (pin "1") (pinfunction "1_1") (pintype "passive"))
      (node (ref "IC7") (pin "2") (pinfunction "V+_2") (pintype "bidirectional"))
    )
    (net (code "91") (name "Net-(IC7A-V-)") (class "Default")
      (node (ref "C25") (pin "1") (pinfunction "1_1") (pintype "passive"))
      (node (ref "IC7") (pin "6") (pinfunction "V-_6") (pintype "bidirectional"))
    )
    (net (code "92") (name "Net-(T1-B)") (class "Default")
      (node (ref "R13") (pin "2") (pinfunction "2_2") (pintype "passive"))
      (node (ref "T1") (pin "1") (pinfunction "B_1") (pintype "passive"))
    )
    (net (code "93") (name "Net-(T1-C)") (class "Default")
      (node (ref "R15") (pin "1") (pinfunction "1_1") (pintype "passive"))
      (node (ref "T1") (pin "3") (pinfunction "C_3") (pintype "passive"))
    )
    (net (code "94") (name "Net-(U$1-READY)") (class "Default")
      (node (ref "R12") (pin "1") (pinfunction "1_1") (pintype "passive"))
      (node (ref "U$1") (pin "6") (pinfunction "READY_6") (pintype "bidirectional"))
    )
    (net (code "95") (name "Net-(U$2-XT)") (class "Default")
      (node (ref "C23") (pin "2") (pinfunction "2_2") (pintype "passive"))
      (node (ref "U$2") (pin "16") (pinfunction "XT_16") (pintype "bidirectional"))
      (node (ref "X2") (pin "2") (pinfunction "2_2") (pintype "passive"))
    )
    (net (code "96") (name "Net-(U$2-~{XT})") (class "Default")
      (node (ref "C20") (pin "2") (pinfunction "2_2") (pintype "passive"))
      (node (ref "U$2") (pin "17") (pinfunction "~{XT}_17") (pintype "bidirectional"))
      (node (ref "X2") (pin "1") (pinfunction "1_1") (pintype "passive"))
    )
    (net (code "97") (name "Net-(U$5-~{CLR})") (class "Default")
      (node (ref "R1") (pin "2") (pinfunction "2_2") (pintype "passive"))
      (node (ref "U$5") (pin "14") (pinfunction "~{CLR}_14") (pintype "bidirectional"))
    )
    (net (code "98") (name "OUT_1") (class "Default")
      (node (ref "SV2") (pin "3") (pinfunction "3_3") (pintype "passive"))
    )
    (net (code "99") (name "OUT_2") (class "Default")
      (node (ref "SV2") (pin "4") (pinfunction "4_4") (pintype "passive"))
    )
    (net (code "100") (name "OUT_3") (class "Default")
      (node (ref "SV2") (pin "5") (pinfunction "5_5") (pintype "passive"))
    )
    (net (code "101") (name "OUT_4") (class "Default")
      (node (ref "SV2") (pin "6") (pinfunction "6_6") (pintype "passive"))
    )
    (net (code "102") (name "RD") (class "Default")
      (node (ref "SV2") (pin "39") (pinfunction "39_39") (pintype "passive"))
      (node (ref "U$1") (pin "3") (pinfunction "~{MEMR}_3") (pintype "bidirectional"))
    )
    (net (code "103") (name "READY") (class "Default")
      (node (ref "SV2") (pin "1") (pinfunction "1_1") (pintype "passive"))
    )
    (net (code "104") (name "RESET") (class "Default")
      (node (ref "IC6") (pin "21") (pinfunction "RESET_21") (pintype "input"))
      (node (ref "SV2") (pin "31") (pinfunction "31_31") (pintype "passive"))
      (node (ref "U$1") (pin "13") (pinfunction "RESET_13") (pintype "bidirectional"))
    )
    (net (code "105") (name "RTC_IRQ") (class "Default")
      (node (ref "IC5") (pin "5") (pinfunction "I_5") (pintype "input"))
      (node (ref "R10") (pin "2") (pinfunction "2_2") (pintype "passive"))
      (node (ref "U$2") (pin "1") (pinfunction "STD.P_1") (pintype "bidirectional"))
    )
    (net (code "106") (name "RTS") (class "Default")
      (node (ref "IC6") (pin "23") (pinfunction "~{RTS}_23") (pintype "output"))
      (node (ref "IC7") (pin "10") (pinfunction "T2IN_10") (pintype "input"))
    )
    (net (code "107") (name "RXD_TTL") (class "Default")
      (node (ref "IC6") (pin "3") (pinfunction "RXD_3") (pintype "input"))
      (node (ref "IC7") (pin "12") (pinfunction "R1OUT_12") (pintype "output"))
    )
    (net (code "108") (name "TC_8257") (class "Default")
      (node (ref "SV2") (pin "54") (pinfunction "54_54") (pintype "passive"))
      (node (ref "U$1") (pin "36") (pinfunction "TC_36") (pintype "bidirectional"))
    )
    (net (code "109") (name "TIMER_CS") (class "Default")
      (node (ref "IC2") (pin "21") (pinfunction "CS_21") (pintype "input"))
      (node (ref "IC4") (pin "11") (pinfunction "Y1_11") (pintype "output"))
    )
    (net (code "110") (name "TIMER_IRQ") (class "Default")
      (node (ref "IC1") (pin "22") (pinfunction "IR4_22") (pintype "input"))
      (node (ref "IC2") (pin "10") (pinfunction "OUT0_10") (pintype "output"))
    )
    (net (code "111") (name "TXD") (class "Default")
      (node (ref "IC6") (pin "19") (pinfunction "TXD_19") (pintype "output"))
      (node (ref "IC7") (pin "11") (pinfunction "T1IN_11") (pintype "input"))
    )
    (net (code "112") (name "UART_BAUD") (class "Default")
      (node (ref "IC2") (pin "17") (pinfunction "OUT2_17") (pintype "output"))
      (node (ref "IC6") (pin "25") (pinfunction "~{RXC}_25") (pintype "input"))
      (node (ref "IC6") (pin "9") (pinfunction "~{TXC}_9") (pintype "input"))
    )
    (net (code "113") (name "UART_CS") (class "Default")
      (node (ref "IC4") (pin "12") (pinfunction "Y0_12") (pintype "output"))
      (node (ref "IC6") (pin "11") (pinfunction "~{CS}_11") (pintype "input"))
    )
    (net (code "114") (name "UART_RX_IRQ") (class "Default")
      (node (ref "IC1") (pin "20") (pinfunction "IR2_20") (pintype "input"))
      (node (ref "IC6") (pin "14") (pinfunction "RXRDY_14") (pintype "output"))
    )
    (net (code "115") (name "UART_TX_IRQ") (class "Default")
      (node (ref "IC1") (pin "19") (pinfunction "IR1_19") (pintype "input"))
      (node (ref "IC6") (pin "15") (pinfunction "TXRDY_15") (pintype "output"))
    )
    (net (code "116") (name "VCC") (class "Default")
      (node (ref "C1") (pin "1") (pinfunction "1_1") (pintype "passive"))
      (node (ref "C10") (pin "1") (pinfunction "1_1") (pintype "passive"))
      (node (ref "C12") (pin "1") (pinfunction "1_1") (pintype "passive"))
      (node (ref "C14") (pin "1") (pinfunction "1_1") (pintype "passive"))
      (node (ref "C15") (pin "1") (pinfunction "1_1") (pintype "passive"))
      (node (ref "C16") (pin "1") (pinfunction "1_1") (pintype "passive"))
      (node (ref "C17") (pin "1") (pinfunction "1_1") (pintype "passive"))
      (node (ref "C19") (pin "1") (pinfunction "1_1") (pintype "passive"))
      (node (ref "C2") (pin "1") (pinfunction "1_1") (pintype "passive"))
      (node (ref "C21") (pin "+") (pinfunction "+_+") (pintype "passive"))
      (node (ref "C24") (pin "+") (pinfunction "+_+") (pintype "passive"))
      (node (ref "C26") (pin "1") (pinfunction "1_1") (pintype "passive"))
      (node (ref "C3") (pin "1") (pinfunction "1_1") (pintype "passive"))
      (node (ref "C6") (pin "2") (pinfunction "2_2") (pintype "passive"))
      (node (ref "D2") (pin "A") (pinfunction "A_A") (pintype "passive"))
      (node (ref "IC1") (pin "28") (pinfunction "VCC_28") (pintype "power_in"))
      (node (ref "IC2") (pin "24") (pinfunction "VCC_24") (pintype "power_in"))
      (node (ref "IC3") (pin "25") (pinfunction "PROG_25") (pintype "bidirectional"))
      (node (ref "IC3") (pin "26") (pinfunction "VDD_26") (pintype "power_in"))
      (node (ref "IC3") (pin "40") (pinfunction "VCC_40") (pintype "power_in"))
      (node (ref "IC4") (pin "16") (pinfunction "VCC_16") (pintype "power_in"))
      (node (ref "IC5") (pin "14") (pinfunction "VCC_14") (pintype "power_in"))
      (node (ref "IC6") (pin "26") (pinfunction "VCC_26") (pintype "power_in"))
      (node (ref "IC7") (pin "16") (pinfunction "VCC_16") (pintype "power_in"))
      (node (ref "IC8") (pin "14") (pinfunction "VCC_14") (pintype "power_in"))
      (node (ref "J1") (pin "5") (pinfunction "5_5") (pintype "bidirectional"))
      (node (ref "JP2") (pin "2") (pinfunction "2_2") (pintype "passive"))
      (node (ref "JP3") (pin "1") (pinfunction "1_1") (pintype "passive"))
      (node (ref "R1") (pin "1") (pinfunction "1_1") (pintype "passive"))
      (node (ref "R10") (pin "1") (pinfunction "1_1") (pintype "passive"))
      (node (ref "R11") (pin "2") (pinfunction "2_2") (pintype "passive"))
      (node (ref "R12") (pin "2") (pinfunction "2_2") (pintype "passive"))
      (node (ref "R14") (pin "2") (pinfunction "2_2") (pintype "passive"))
      (node (ref "R17") (pin "2") (pinfunction "2_2") (pintype "passive"))
      (node (ref "R19") (pin "2") (pinfunction "2_2") (pintype "passive"))
      (node (ref "R2") (pin "1") (pinfunction "1_1") (pintype "passive"))
      (node (ref "R7") (pin "2") (pinfunction "2_2") (pintype "passive"))
      (node (ref "R8") (pin "2") (pinfunction "2_2") (pintype "passive"))
      (node (ref "R9") (pin "1") (pinfunction "1_1") (pintype "passive"))
      (node (ref "U$1") (pin "31") (pinfunction "VCC_31") (pintype "bidirectional"))
      (node (ref "U$2") (pin "15") (pinfunction "CS1_15") (pintype "bidirectional"))
      (node (ref "U$2") (pin "3") (pinfunction "ALE_3") (pintype "bidirectional"))
      (node (ref "U$5") (pin "24") (pinfunction "VCC_24") (pintype "bidirectional"))
    )
    (net (code "117") (name "VPA") (class "Default")
      (node (ref "C13") (pin "2") (pinfunction "2_2") (pintype "passive"))
      (node (ref "C18") (pin "+") (pinfunction "+_+") (pintype "passive"))
      (node (ref "D1") (pin "C") (pinfunction "C_C") (pintype "passive"))
      (node (ref "D2") (pin "C") (pinfunction "C_C") (pintype "passive"))
      (node (ref "U$2") (pin "18") (pinfunction "VDD_18") (pintype "bidirectional"))
    )
    (net (code "118") (name "WR") (class "Default")
      (node (ref "SV2") (pin "40") (pinfunction "40_40") (pintype "passive"))
      (node (ref "U$1") (pin "4") (pinfunction "~{MEMW}_4") (pintype "bidirectional"))
    )
    (net (code "119") (name "unconnected-(IC1A-CAS0-Pad12)") (class "Default")
      (node (ref "IC1") (pin "12") (pinfunction "CAS0_12") (pintype "bidirectional"))
    )
    (net (code "120") (name "unconnected-(IC1A-CAS1-Pad13)") (class "Default")
      (node (ref "IC1") (pin "13") (pinfunction "CAS1_13") (pintype "bidirectional"))
    )
    (net (code "121") (name "unconnected-(IC1A-CAS2-Pad15)") (class "Default")
      (node (ref "IC1") (pin "15") (pinfunction "CAS2_15") (pintype "bidirectional"))
    )
    (net (code "122") (name "unconnected-(IC3-P10-Pad27)") (class "Default")
      (node (ref "IC3") (pin "27") (pinfunction "P10_27") (pintype "bidirectional"))
    )
    (net (code "123") (name "unconnected-(IC3-P11-Pad28)") (class "Default")
      (node (ref "IC3") (pin "28") (pinfunction "P11_28") (pintype "bidirectional"))
    )
    (net (code "124") (name "unconnected-(IC3-P12-Pad29)") (class "Default")
      (node (ref "IC3") (pin "29") (pinfunction "P12_29") (pintype "bidirectional"))
    )
    (net (code "125") (name "unconnected-(IC3-P13-Pad30)") (class "Default")
      (node (ref "IC3") (pin "30") (pinfunction "P13_30") (pintype "bidirectional"))
    )
    (net (code "126") (name "unconnected-(IC3-P14-Pad31)") (class "Default")
      (node (ref "IC3") (pin "31") (pinfunction "P14_31") (pintype "bidirectional"))
    )
    (net (code "127") (name "unconnected-(IC3-P15-Pad32)") (class "Default")
      (node (ref "IC3") (pin "32") (pinfunction "P15_32") (pintype "bidirectional"))
    )
    (net (code "128") (name "unconnected-(IC3-P16-Pad33)") (class "Default")
      (node (ref "IC3") (pin "33") (pinfunction "P16_33") (pintype "bidirectional"))
    )
    (net (code "129") (name "unconnected-(IC3-P17-Pad34)") (class "Default")
      (node (ref "IC3") (pin "34") (pinfunction "P17_34") (pintype "bidirectional"))
    )
    (net (code "130") (name "unconnected-(IC3-P20-Pad21)") (class "Default")
      (node (ref "IC3") (pin "21") (pinfunction "P20_21") (pintype "bidirectional"))
    )
    (net (code "131") (name "unconnected-(IC3-P21-Pad22)") (class "Default")
      (node (ref "IC3") (pin "22") (pinfunction "P21_22") (pintype "bidirectional"))
    )
    (net (code "132") (name "unconnected-(IC3-P25{slash}~{IBF}-Pad36)") (class "Default")
      (node (ref "IC3") (pin "36") (pinfunction "P25/~{IBF}_36") (pintype "bidirectional"))
    )
    (net (code "133") (name "unconnected-(IC3-SYNC-Pad11)") (class "Default")
      (node (ref "IC3") (pin "11") (pinfunction "SYNC_11") (pintype "output"))
    )
    (net (code "134") (name "unconnected-(IC4A-Y2-Pad6)") (class "Default")
      (node (ref "IC4") (pin "6") (pinfunction "Y2_6") (pintype "output"))
    )
    (net (code "135") (name "unconnected-(IC4A-Y3-Pad7)") (class "Default")
      (node (ref "IC4") (pin "7") (pinfunction "Y3_7") (pintype "output"))
    )
    (net (code "136") (name "unconnected-(IC5D-O-Pad8)") (class "Default")
      (node (ref "IC5") (pin "8") (pinfunction "O_8") (pintype "open_collector"))
    )
    (net (code "137") (name "unconnected-(IC5E-O-Pad10)") (class "Default")
      (node (ref "IC5") (pin "10") (pinfunction "O_10") (pintype "open_collector"))
    )
    (net (code "138") (name "unconnected-(IC6-SYNDET-Pad16)") (class "Default")
      (node (ref "IC6") (pin "16") (pinfunction "SYNDET_16") (pintype "bidirectional"))
    )
    (net (code "139") (name "unconnected-(IC6-TXE-Pad18)") (class "Default")
      (node (ref "IC6") (pin "18") (pinfunction "TXE_18") (pintype "output"))
    )
    (net (code "140") (name "unconnected-(IC6-~{DTR}-Pad24)") (class "Default")
      (node (ref "IC6") (pin "24") (pinfunction "~{DTR}_24") (pintype "output"))
    )
    (net (code "141") (name "unconnected-(IC8A-O-Pad2)") (class "Default")
      (node (ref "IC8") (pin "2") (pinfunction "O_2") (pintype "output"))
    )
    (net (code "142") (name "unconnected-(IC8B-O-Pad4)") (class "Default")
      (node (ref "IC8") (pin "4") (pinfunction "O_4") (pintype "output"))
    )
    (net (code "143") (name "unconnected-(IC8E-O-Pad10)") (class "Default")
      (node (ref "IC8") (pin "10") (pinfunction "O_10") (pintype "output"))
    )
    (net (code "144") (name "unconnected-(IC8F-O-Pad12)") (class "Default")
      (node (ref "IC8") (pin "12") (pinfunction "O_12") (pintype "output"))
    )
    (net (code "145") (name "unconnected-(J1-Pad3)") (class "Default")
      (node (ref "J1") (pin "3") (pinfunction "3_3") (pintype "bidirectional"))
    )
    (net (code "146") (name "unconnected-(SV2-Pad53)") (class "Default")
      (node (ref "SV2") (pin "53") (pinfunction "53_53") (pintype "passive"))
    )
    (net (code "147") (name "unconnected-(SV2-Pad55)") (class "Default")
      (node (ref "SV2") (pin "55") (pinfunction "55_55") (pintype "passive"))
    )
    (net (code "148") (name "unconnected-(SV2-Pad56)") (class "Default")
      (node (ref "SV2") (pin "56") (pinfunction "56_56") (pintype "passive"))
    )
    (net (code "149") (name "unconnected-(SV2-Pad64)") (class "Default")
      (node (ref "SV2") (pin "64") (pinfunction "64_64") (pintype "passive"))
    )
    (net (code "150") (name "unconnected-(U$1-MARK-Pad5)") (class "Default")
      (node (ref "U$1") (pin "5") (pinfunction "MARK_5") (pintype "bidirectional"))
    )
    (net (code "151") (name "unconnected-(U$5-~{INT}-Pad23)") (class "Default")
      (node (ref "U$5") (pin "23") (pinfunction "~{INT}_23") (pintype "bidirectional"))
    )
    (net (code "152") (name "unconnected-(X1-Pad1)") (class "Default")
      (node (ref "X1") (pin "1") (pinfunction "1_1") (pintype "passive"))
    )
    (net (code "153") (name "unconnected-(X1-Pad4)") (class "Default")
      (node (ref "X1") (pin "4") (pinfunction "4_4") (pintype "passive"))
    )
    (net (code "154") (name "unconnected-(X1-Pad6)") (class "Default")
      (node (ref "X1") (pin "6") (pinfunction "6_6") (pintype "passive"))
    )
    (net (code "155") (name "unconnected-(X1-Pad9)") (class "Default")
      (node (ref "X1") (pin "9") (pinfunction "9_9") (pintype "passive"))
    )
  )
)
